# IR_Sensor.net
KiCad netlist of a schematic drawn in EAGLE
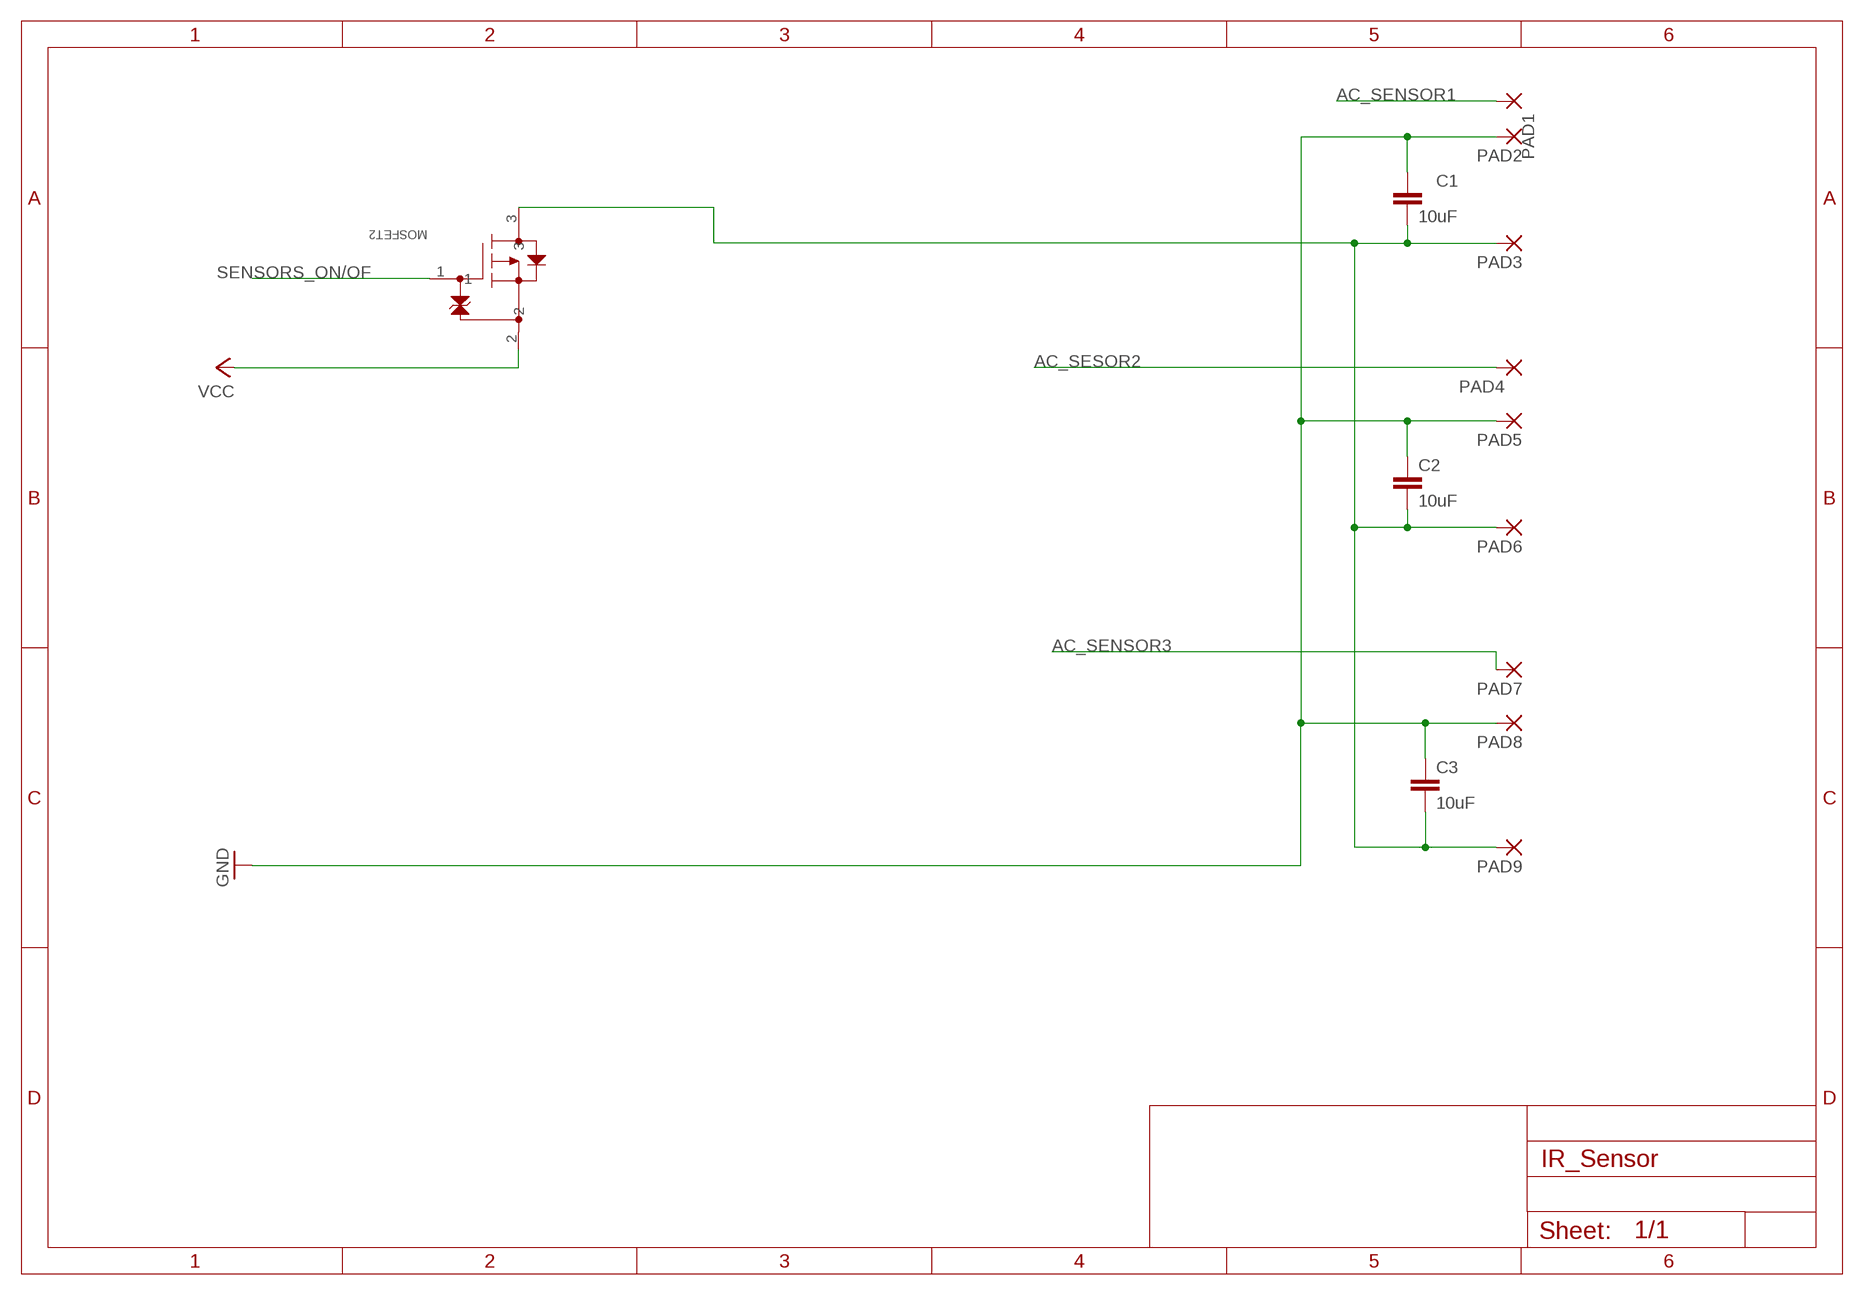
[diagram p0: schematic, sheet 1]

(export (version "E")
  (design (tool "Eeschema 10.0.6"))
  (components
    (comp (ref "C1")
      (value "10uF")
      (footprint "eagle-import:C0805")
      (libsource (lib "eagle-import") (part "C-EUC0805"))
    )
    (comp (ref "C2")
      (value "10uF")
      (footprint "eagle-import:C0805")
      (libsource (lib "eagle-import") (part "C-EUC0805"))
    )
    (comp (ref "C3")
      (value "10uF")
      (footprint "eagle-import:C0805")
      (libsource (lib "eagle-import") (part "C-EUC0805"))
    )
    (comp (ref "MOSFET2")
      (value "SSM3J117TU(TE85L)")
      (footprint "eagle-import:UFM_TOS")
      (fields (field (name "COPYRIGHT") "Copyright (C) 2022 Ultra Librarian. All rights reserved."))
      (libsource (lib "eagle-import") (part "SSM3J117TU(TE85L)"))
    )
    (comp (ref "PAD1")
      (value "1,6/0,8")
      (footprint "eagle-import:1,6_0,8")
      (libsource (lib "eagle-import") (part "1,6/0,8"))
    )
    (comp (ref "PAD2")
      (value "1,6/0,8")
      (footprint "eagle-import:1,6_0,8")
      (libsource (lib "eagle-import") (part "1,6/0,8"))
    )
    (comp (ref "PAD3")
      (value "1,6/0,8")
      (footprint "eagle-import:1,6_0,8")
      (libsource (lib "eagle-import") (part "1,6/0,8"))
    )
    (comp (ref "PAD4")
      (value "1,6/0,8")
      (footprint "eagle-import:1,6_0,8")
      (libsource (lib "eagle-import") (part "1,6/0,8"))
    )
    (comp (ref "PAD5")
      (value "1,6/0,8")
      (footprint "eagle-import:1,6_0,8")
      (libsource (lib "eagle-import") (part "1,6/0,8"))
    )
    (comp (ref "PAD6")
      (value "1,6/0,8")
      (footprint "eagle-import:1,6_0,8")
      (libsource (lib "eagle-import") (part "1,6/0,8"))
    )
    (comp (ref "PAD7")
      (value "1,6/0,8")
      (footprint "eagle-import:1,6_0,8")
      (libsource (lib "eagle-import") (part "1,6/0,8"))
    )
    (comp (ref "PAD8")
      (value "1,6/0,8")
      (footprint "eagle-import:1,6_0,8")
      (libsource (lib "eagle-import") (part "1,6/0,8"))
    )
    (comp (ref "PAD9")
      (value "1,6/0,8")
      (footprint "eagle-import:1,6_0,8")
      (libsource (lib "eagle-import") (part "1,6/0,8"))
    )
  )
  (nets
    (net (code "1") (name "/AC_SENSOR1") (class "Default")
      (node (ref "PAD1") (pin "1") (pinfunction "P_1") (pintype "passive"))
    )
    (net (code "2") (name "/AC_SENSOR3") (class "Default")
      (node (ref "PAD7") (pin "1") (pinfunction "P_1") (pintype "passive"))
    )
    (net (code "3") (name "/AC_SESOR2") (class "Default")
      (node (ref "PAD4") (pin "1") (pinfunction "P_1") (pintype "passive"))
    )
    (net (code "4") (name "/SENSORS_ON{slash}OF") (class "Default")
      (node (ref "MOSFET2") (pin "1") (pinfunction "1_1") (pintype "passive"))
    )
    (net (code "5") (name "GND") (class "Default")
      (node (ref "C1") (pin "1") (pinfunction "1_1") (pintype "passive"))
      (node (ref "C2") (pin "1") (pinfunction "1_1") (pintype "passive"))
      (node (ref "C3") (pin "1") (pinfunction "1_1") (pintype "passive"))
      (node (ref "PAD2") (pin "1") (pinfunction "P_1") (pintype "passive"))
      (node (ref "PAD5") (pin "1") (pinfunction "P_1") (pintype "passive"))
      (node (ref "PAD8") (pin "1") (pinfunction "P_1") (pintype "passive"))
    )
    (net (code "6") (name "Net-(PAD3-P)") (class "Default")
      (node (ref "C1") (pin "2") (pinfunction "2_2") (pintype "passive"))
      (node (ref "C2") (pin "2") (pinfunction "2_2") (pintype "passive"))
      (node (ref "C3") (pin "2") (pinfunction "2_2") (pintype "passive"))
      (node (ref "MOSFET2") (pin "3") (pinfunction "3_3") (pintype "passive"))
      (node (ref "PAD3") (pin "1") (pinfunction "P_1") (pintype "passive"))
      (node (ref "PAD6") (pin "1") (pinfunction "P_1") (pintype "passive"))
      (node (ref "PAD9") (pin "1") (pinfunction "P_1") (pintype "passive"))
    )
    (net (code "7") (name "VCC") (class "Default")
      (node (ref "MOSFET2") (pin "2") (pinfunction "2_2") (pintype "passive"))
    )
  )
)
